# FUNCTION_EFUSE.net
KiCad netlist of a schematic drawn in Altium Designer
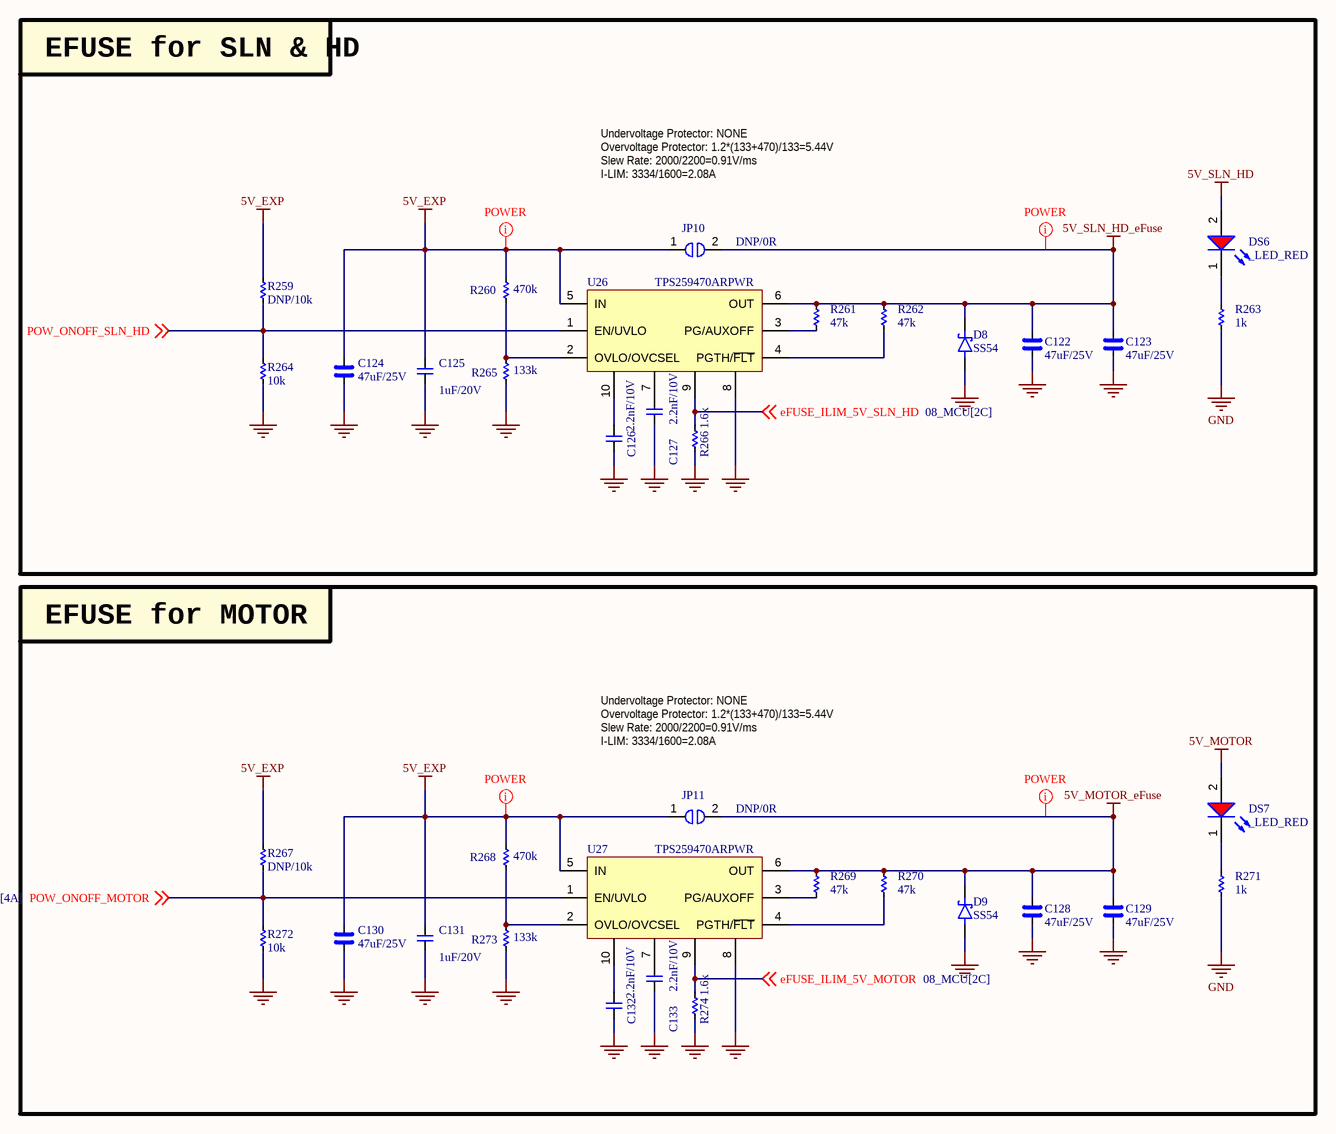
[diagram p0: FUNCTION_EFUSE.SchDoc]

(export (version "E")
  (design (tool "Eeschema 10.0.6"))
  (components
    (comp (ref "C122")
      (value "47uF/25V")
      (footprint "CAP_C_3225X80")
      (description "CAP High Value")
      (libsource (lib "LABLIB") (part "_CAP_C_High_2"))
    )
    (comp (ref "C123")
      (value "47uF/25V")
      (footprint "CAP_C_3225X80")
      (description "CAP High Value")
      (libsource (lib "LABLIB") (part "_CAP_C_High_2"))
    )
    (comp (ref "C124")
      (value "47uF/25V")
      (footprint "CAP_C_3225X80")
      (description "CAP High Value")
      (libsource (lib "LABLIB") (part "_CAP_C_High_2"))
    )
    (comp (ref "C125")
      (value "1uF/20V")
      (footprint "CAP_C_1005X50_L")
      (description "CAP")
      (libsource (lib "LABLIB") (part "_CAP_C_2"))
    )
    (comp (ref "C126")
      (value "2.2nF/10V")
      (footprint "CAP_C_1005X50_L")
      (description "CAP")
      (libsource (lib "LABLIB") (part "_CAP_C_2"))
    )
    (comp (ref "C127")
      (value "2.2nF/10V")
      (footprint "CAP_C_1005X50_L")
      (description "CAP")
      (libsource (lib "LABLIB") (part "_CAP_C_2"))
    )
    (comp (ref "C128")
      (value "47uF/25V")
      (footprint "CAP_C_3225X80")
      (description "CAP High Value")
      (libsource (lib "LABLIB") (part "_CAP_C_High_2"))
    )
    (comp (ref "C129")
      (value "47uF/25V")
      (footprint "CAP_C_3225X80")
      (description "CAP High Value")
      (libsource (lib "LABLIB") (part "_CAP_C_High_2"))
    )
    (comp (ref "C130")
      (value "47uF/25V")
      (footprint "CAP_C_3225X80")
      (description "CAP High Value")
      (libsource (lib "LABLIB") (part "_CAP_C_High_2"))
    )
    (comp (ref "C131")
      (value "1uF/20V")
      (footprint "CAP_C_1005X50_L")
      (description "CAP")
      (libsource (lib "LABLIB") (part "_CAP_C_2"))
    )
    (comp (ref "C132")
      (value "2.2nF/10V")
      (footprint "CAP_C_1005X50_L")
      (description "CAP")
      (libsource (lib "LABLIB") (part "_CAP_C_2"))
    )
    (comp (ref "C133")
      (value "2.2nF/10V")
      (footprint "CAP_C_1005X50_L")
      (description "CAP")
      (libsource (lib "LABLIB") (part "_CAP_C_2"))
    )
    (comp (ref "D8")
      (value "SS54")
      (footprint "DO-214AC_SMA")
      (description "DIODE SCHOTTKY")
      (libsource (lib "LABLIB") (part "DIODE SCHOTTKY"))
    )
    (comp (ref "D9")
      (value "SS54")
      (footprint "DO-214AC_SMA")
      (description "DIODE SCHOTTKY")
      (libsource (lib "LABLIB") (part "DIODE SCHOTTKY"))
    )
    (comp (ref "DS6") (value "_LED_RED") (footprint "LED_0603") (libsource (lib "LABLIB") (part "_LED_RED")))
    (comp (ref "DS7") (value "_LED_RED") (footprint "LED_0603") (libsource (lib "LABLIB") (part "_LED_RED")))
    (comp (ref "JP10")
      (value "DNP/0R")
      (footprint "JUMPER_1608")
      (libsource (lib "BEE-DAL_EXP_sche") (part "JUMPER_1_1"))
    )
    (comp (ref "JP11")
      (value "DNP/0R")
      (footprint "JUMPER_1608")
      (libsource (lib "BEE-DAL_EXP_sche") (part "JUMPER_1_1"))
    )
    (comp (ref "R259")
      (value "DNP/10k")
      (footprint "RES_C_1005X40")
      (description "RES")
      (libsource (lib "LABLIB") (part "_RES_B_2"))
    )
    (comp (ref "R260")
      (value "470k")
      (footprint "RES_C_1005X40")
      (description "RES")
      (libsource (lib "LABLIB") (part "_RES_B_2"))
    )
    (comp (ref "R261")
      (value "47k")
      (footprint "RES_C_1005X40")
      (description "RES")
      (libsource (lib "LABLIB") (part "_RES_B_2"))
    )
    (comp (ref "R262")
      (value "47k")
      (footprint "RES_C_1005X40")
      (description "RES")
      (libsource (lib "LABLIB") (part "_RES_B_2"))
    )
    (comp (ref "R263")
      (value "1k")
      (footprint "RES_C_1005X40")
      (description "RES")
      (libsource (lib "LABLIB") (part "_RES_B_2"))
    )
    (comp (ref "R264")
      (value "10k")
      (footprint "RES_C_1005X40")
      (description "RES")
      (libsource (lib "LABLIB") (part "_RES_B_2"))
    )
    (comp (ref "R265")
      (value "133k")
      (footprint "RES_C_1005X40")
      (description "RES")
      (libsource (lib "LABLIB") (part "_RES_B_2"))
    )
    (comp (ref "R266")
      (value "1.6k")
      (footprint "RES_C_1005X40")
      (description "RES")
      (libsource (lib "LABLIB") (part "_RES_B_2"))
    )
    (comp (ref "R267")
      (value "DNP/10k")
      (footprint "RES_C_1005X40")
      (description "RES")
      (libsource (lib "LABLIB") (part "_RES_B_2"))
    )
    (comp (ref "R268")
      (value "470k")
      (footprint "RES_C_1005X40")
      (description "RES")
      (libsource (lib "LABLIB") (part "_RES_B_2"))
    )
    (comp (ref "R269")
      (value "47k")
      (footprint "RES_C_1005X40")
      (description "RES")
      (libsource (lib "LABLIB") (part "_RES_B_2"))
    )
    (comp (ref "R270")
      (value "47k")
      (footprint "RES_C_1005X40")
      (description "RES")
      (libsource (lib "LABLIB") (part "_RES_B_2"))
    )
    (comp (ref "R271")
      (value "1k")
      (footprint "RES_C_1005X40")
      (description "RES")
      (libsource (lib "LABLIB") (part "_RES_B_2"))
    )
    (comp (ref "R272")
      (value "10k")
      (footprint "RES_C_1005X40")
      (description "RES")
      (libsource (lib "LABLIB") (part "_RES_B_2"))
    )
    (comp (ref "R273")
      (value "133k")
      (footprint "RES_C_1005X40")
      (description "RES")
      (libsource (lib "LABLIB") (part "_RES_B_2"))
    )
    (comp (ref "R274")
      (value "1.6k")
      (footprint "RES_C_1005X40")
      (description "RES")
      (libsource (lib "LABLIB") (part "_RES_B_2"))
    )
    (comp (ref "U26")
      (value "TPS259470ARPWR")
      (footprint "VQFN-HR-10")
      (libsource (lib "BEE-DAL_EXP_sche") (part "TPS259470ARPWR"))
    )
    (comp (ref "U27")
      (value "TPS259470ARPWR")
      (footprint "VQFN-HR-10")
      (libsource (lib "BEE-DAL_EXP_sche") (part "TPS259470ARPWR"))
    )
  )
  (nets
    (net (code "1") (name "5V_EXP") (class "Default")
      (node (ref "C124") (pin "2") (pinfunction "2_2") (pintype "passive"))
      (node (ref "C125") (pin "2") (pinfunction "2_2") (pintype "passive"))
      (node (ref "C130") (pin "2") (pinfunction "2_2") (pintype "passive"))
      (node (ref "C131") (pin "2") (pinfunction "2_2") (pintype "passive"))
      (node (ref "JP10") (pin "1") (pinfunction "1_1") (pintype "passive"))
      (node (ref "JP11") (pin "1") (pinfunction "1_1") (pintype "passive"))
      (node (ref "R259") (pin "1") (pinfunction "1_1") (pintype "passive"))
      (node (ref "R260") (pin "2") (pinfunction "2_2") (pintype "passive"))
      (node (ref "R267") (pin "1") (pinfunction "1_1") (pintype "passive"))
      (node (ref "R268") (pin "2") (pinfunction "2_2") (pintype "passive"))
      (node (ref "U26") (pin "5") (pinfunction "IN_5") (pintype "passive"))
      (node (ref "U27") (pin "5") (pinfunction "IN_5") (pintype "passive"))
    )
    (net (code "2") (name "5V_MOTOR") (class "Default")
      (node (ref "DS7") (pin "2") (pinfunction "A_2") (pintype "passive"))
    )
    (net (code "3") (name "5V_MOTOR_eFuse") (class "Default")
      (node (ref "C128") (pin "2") (pinfunction "2_2") (pintype "passive"))
      (node (ref "C129") (pin "2") (pinfunction "2_2") (pintype "passive"))
      (node (ref "D9") (pin "1") (pinfunction "K_1") (pintype "passive"))
      (node (ref "JP11") (pin "2") (pinfunction "2_2") (pintype "passive"))
      (node (ref "R269") (pin "2") (pinfunction "2_2") (pintype "passive"))
      (node (ref "R270") (pin "2") (pinfunction "2_2") (pintype "passive"))
      (node (ref "U27") (pin "6") (pinfunction "OUT_6") (pintype "passive"))
    )
    (net (code "4") (name "5V_SLN_HD") (class "Default")
      (node (ref "DS6") (pin "2") (pinfunction "A_2") (pintype "passive"))
    )
    (net (code "5") (name "5V_SLN_HD_eFuse") (class "Default")
      (node (ref "C122") (pin "2") (pinfunction "2_2") (pintype "passive"))
      (node (ref "C123") (pin "2") (pinfunction "2_2") (pintype "passive"))
      (node (ref "D8") (pin "1") (pinfunction "K_1") (pintype "passive"))
      (node (ref "JP10") (pin "2") (pinfunction "2_2") (pintype "passive"))
      (node (ref "R261") (pin "2") (pinfunction "2_2") (pintype "passive"))
      (node (ref "R262") (pin "2") (pinfunction "2_2") (pintype "passive"))
      (node (ref "U26") (pin "6") (pinfunction "OUT_6") (pintype "passive"))
    )
    (net (code "6") (name "GND") (class "Default")
      (node (ref "C122") (pin "1") (pinfunction "1_1") (pintype "passive"))
      (node (ref "C123") (pin "1") (pinfunction "1_1") (pintype "passive"))
      (node (ref "C124") (pin "1") (pinfunction "1_1") (pintype "passive"))
      (node (ref "C125") (pin "1") (pinfunction "1_1") (pintype "passive"))
      (node (ref "C126") (pin "1") (pinfunction "1_1") (pintype "passive"))
      (node (ref "C127") (pin "1") (pinfunction "1_1") (pintype "passive"))
      (node (ref "C128") (pin "1") (pinfunction "1_1") (pintype "passive"))
      (node (ref "C129") (pin "1") (pinfunction "1_1") (pintype "passive"))
      (node (ref "C130") (pin "1") (pinfunction "1_1") (pintype "passive"))
      (node (ref "C131") (pin "1") (pinfunction "1_1") (pintype "passive"))
      (node (ref "C132") (pin "1") (pinfunction "1_1") (pintype "passive"))
      (node (ref "C133") (pin "1") (pinfunction "1_1") (pintype "passive"))
      (node (ref "D8") (pin "2") (pinfunction "A_2") (pintype "passive"))
      (node (ref "D9") (pin "2") (pinfunction "A_2") (pintype "passive"))
      (node (ref "R263") (pin "1") (pinfunction "1_1") (pintype "passive"))
      (node (ref "R264") (pin "2") (pinfunction "2_2") (pintype "passive"))
      (node (ref "R265") (pin "1") (pinfunction "1_1") (pintype "passive"))
      (node (ref "R266") (pin "1") (pinfunction "1_1") (pintype "passive"))
      (node (ref "R271") (pin "1") (pinfunction "1_1") (pintype "passive"))
      (node (ref "R272") (pin "2") (pinfunction "2_2") (pintype "passive"))
      (node (ref "R273") (pin "1") (pinfunction "1_1") (pintype "passive"))
      (node (ref "R274") (pin "1") (pinfunction "1_1") (pintype "passive"))
      (node (ref "U26") (pin "8") (pinfunction "8_8") (pintype "passive"))
      (node (ref "U27") (pin "8") (pinfunction "8_8") (pintype "passive"))
    )
    (net (code "7") (name "Net-(C126-Pad2)") (class "Default")
      (node (ref "C126") (pin "2") (pinfunction "2_2") (pintype "passive"))
      (node (ref "U26") (pin "10") (pinfunction "10_10") (pintype "passive"))
    )
    (net (code "8") (name "Net-(C127-Pad2)") (class "Default")
      (node (ref "C127") (pin "2") (pinfunction "2_2") (pintype "passive"))
      (node (ref "U26") (pin "7") (pinfunction "7_7") (pintype "passive"))
    )
    (net (code "9") (name "Net-(C132-Pad2)") (class "Default")
      (node (ref "C132") (pin "2") (pinfunction "2_2") (pintype "passive"))
      (node (ref "U27") (pin "10") (pinfunction "10_10") (pintype "passive"))
    )
    (net (code "10") (name "Net-(C133-Pad2)") (class "Default")
      (node (ref "C133") (pin "2") (pinfunction "2_2") (pintype "passive"))
      (node (ref "U27") (pin "7") (pinfunction "7_7") (pintype "passive"))
    )
    (net (code "11") (name "Net-(DS6-K)") (class "Default")
      (node (ref "DS6") (pin "1") (pinfunction "K_1") (pintype "passive"))
      (node (ref "R263") (pin "2") (pinfunction "2_2") (pintype "passive"))
    )
    (net (code "12") (name "Net-(DS7-K)") (class "Default")
      (node (ref "DS7") (pin "1") (pinfunction "K_1") (pintype "passive"))
      (node (ref "R271") (pin "2") (pinfunction "2_2") (pintype "passive"))
    )
    (net (code "13") (name "Net-(U26-OVLO{slash}OVCSEL)") (class "Default")
      (node (ref "R260") (pin "1") (pinfunction "1_1") (pintype "passive"))
      (node (ref "R265") (pin "2") (pinfunction "2_2") (pintype "passive"))
      (node (ref "U26") (pin "2") (pinfunction "OVLO/OVCSEL_2") (pintype "passive"))
    )
    (net (code "14") (name "Net-(U26-PGTH{slash}~{FLT})") (class "Default")
      (node (ref "R262") (pin "1") (pinfunction "1_1") (pintype "passive"))
      (node (ref "U26") (pin "4") (pinfunction "PGTH/~{FLT}_4") (pintype "passive"))
    )
    (net (code "15") (name "Net-(U26-PG{slash}AUXOFF)") (class "Default")
      (node (ref "R261") (pin "1") (pinfunction "1_1") (pintype "passive"))
      (node (ref "U26") (pin "3") (pinfunction "PG/AUXOFF_3") (pintype "passive"))
    )
    (net (code "16") (name "Net-(U27-OVLO{slash}OVCSEL)") (class "Default")
      (node (ref "R268") (pin "1") (pinfunction "1_1") (pintype "passive"))
      (node (ref "R273") (pin "2") (pinfunction "2_2") (pintype "passive"))
      (node (ref "U27") (pin "2") (pinfunction "OVLO/OVCSEL_2") (pintype "passive"))
    )
    (net (code "17") (name "Net-(U27-PGTH{slash}~{FLT})") (class "Default")
      (node (ref "R270") (pin "1") (pinfunction "1_1") (pintype "passive"))
      (node (ref "U27") (pin "4") (pinfunction "PGTH/~{FLT}_4") (pintype "passive"))
    )
    (net (code "18") (name "Net-(U27-PG{slash}AUXOFF)") (class "Default")
      (node (ref "R269") (pin "1") (pinfunction "1_1") (pintype "passive"))
      (node (ref "U27") (pin "3") (pinfunction "PG/AUXOFF_3") (pintype "passive"))
    )
    (net (code "19") (name "POW_ONOFF_MOTOR") (class "Default")
      (node (ref "R267") (pin "2") (pinfunction "2_2") (pintype "passive"))
      (node (ref "R272") (pin "1") (pinfunction "1_1") (pintype "passive"))
      (node (ref "U27") (pin "1") (pinfunction "EN/UVLO_1") (pintype "passive"))
    )
    (net (code "20") (name "POW_ONOFF_SLN_HD") (class "Default")
      (node (ref "R259") (pin "2") (pinfunction "2_2") (pintype "passive"))
      (node (ref "R264") (pin "1") (pinfunction "1_1") (pintype "passive"))
      (node (ref "U26") (pin "1") (pinfunction "EN/UVLO_1") (pintype "passive"))
    )
    (net (code "21") (name "eFUSE_ILIM_5V_MOTOR") (class "Default")
      (node (ref "R274") (pin "2") (pinfunction "2_2") (pintype "passive"))
      (node (ref "U27") (pin "9") (pinfunction "9_9") (pintype "passive"))
    )
    (net (code "22") (name "eFUSE_ILIM_5V_SLN_HD") (class "Default")
      (node (ref "R266") (pin "2") (pinfunction "2_2") (pintype "passive"))
      (node (ref "U26") (pin "9") (pinfunction "9_9") (pintype "passive"))
    )
  )
)
